# V4-AddOnZigbee-SMD-V002.net
KiCad netlist of a schematic drawn in EAGLE
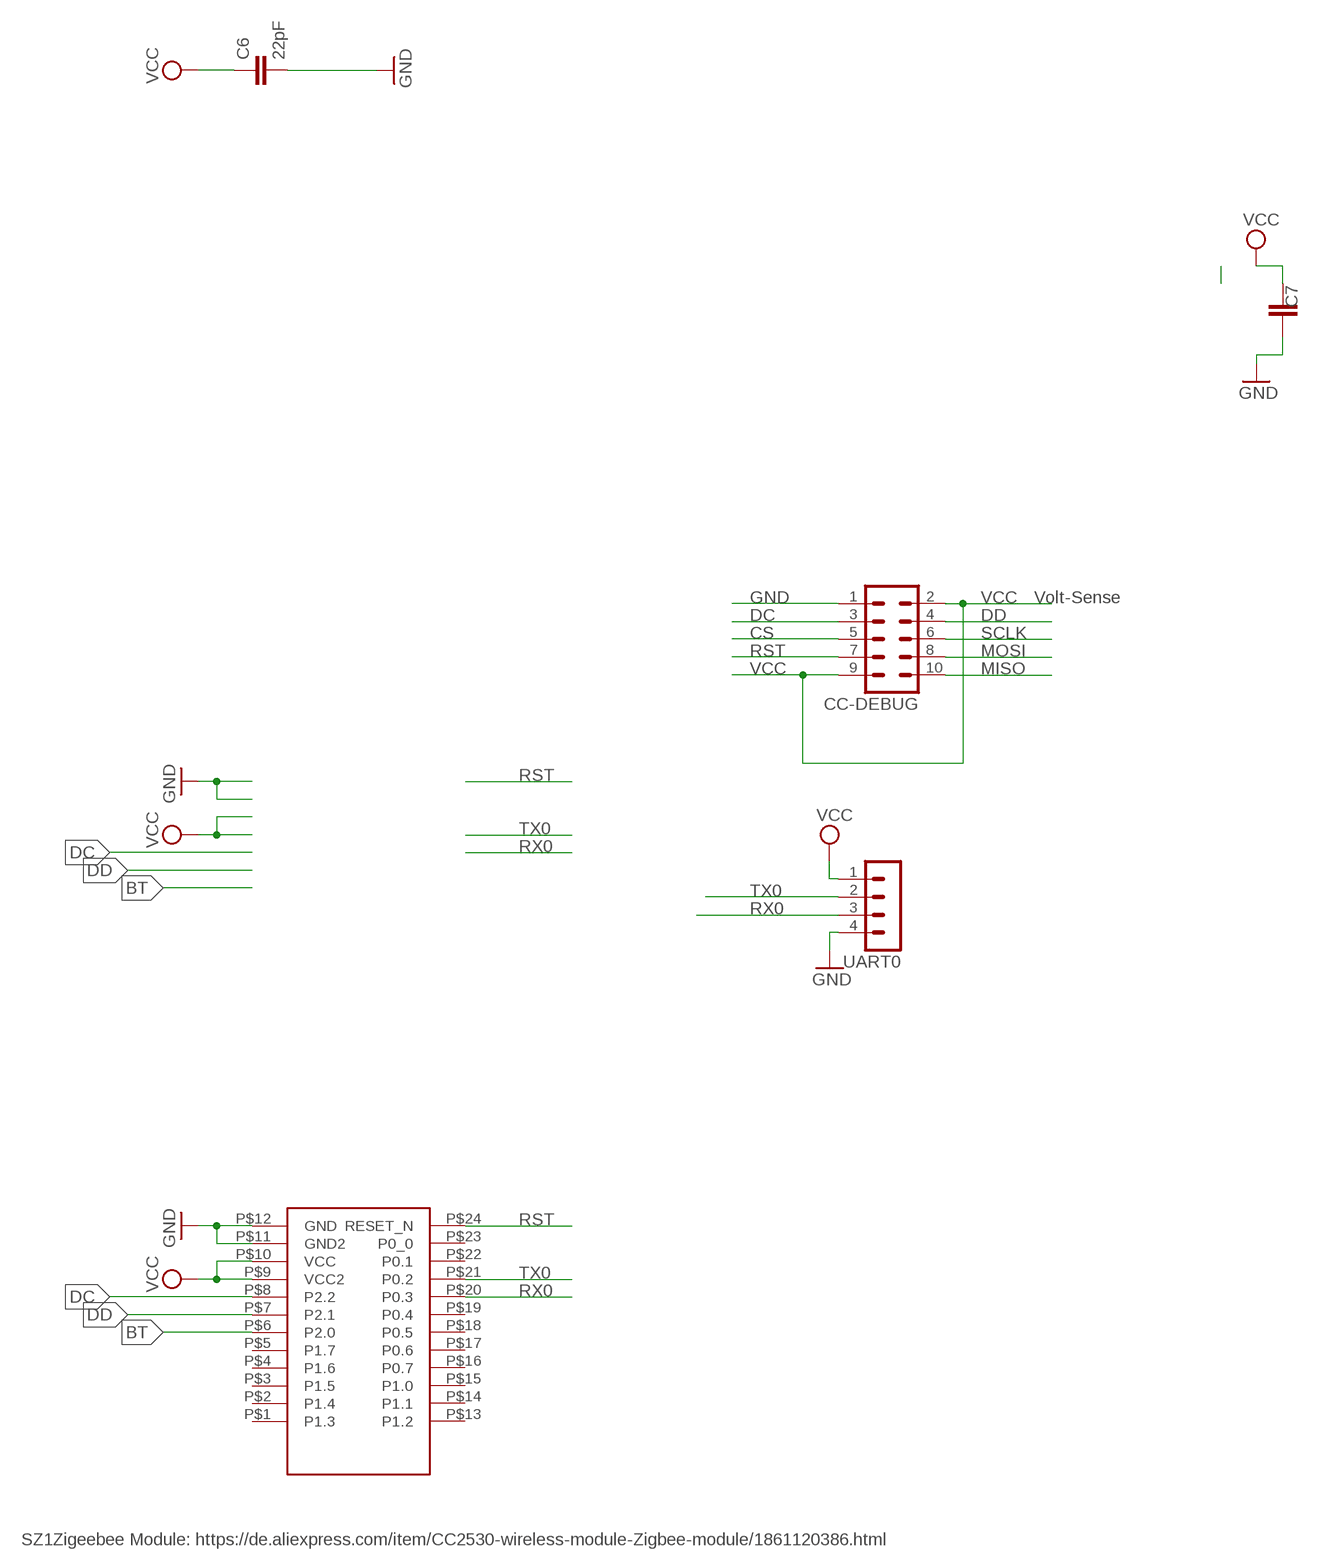
[diagram p0: schematic, sheet 1]

(export (version "E")
  (design (tool "Eeschema 10.0.6"))
  (components
    (comp (ref "C6")
      (value "22pF")
      (footprint "eagle-import:C0805")
      (libsource (lib "eagle-import") (part "C-EUC0805"))
    )
    (comp (ref "C7")
      (value "C-EUC1812")
      (footprint "eagle-import:C1812")
      (libsource (lib "eagle-import") (part "C-EUC1812"))
    )
    (comp (ref "CC-DEBUG")
      (value "MA05-2")
      (footprint "eagle-import:MA05-2")
      (libsource (lib "eagle-import") (part "MA05-2"))
    )
    (comp (ref "U$1")
      (value "CC2530")
      (footprint "eagle-import:SZ1ZIGBEE-SMD")
      (libsource (lib "eagle-import") (part "CC2530"))
    )
    (comp (ref "UART0")
      (value "MA04-1")
      (footprint "eagle-import:MA04-1")
      (libsource (lib "eagle-import") (part "MA04-1"))
    )
  )
  (nets
    (net (code "1") (name "/CS") (class "Default")
      (node (ref "CC-DEBUG") (pin "5") (pinfunction "5_5") (pintype "passive"))
    )
    (net (code "2") (name "/MISO") (class "Default")
      (node (ref "CC-DEBUG") (pin "10") (pinfunction "10_10") (pintype "passive"))
    )
    (net (code "3") (name "/MOSI") (class "Default")
      (node (ref "CC-DEBUG") (pin "8") (pinfunction "8_8") (pintype "passive"))
    )
    (net (code "4") (name "/RST") (class "Default")
      (node (ref "CC-DEBUG") (pin "7") (pinfunction "7_7") (pintype "passive"))
      (node (ref "U$1") (pin "P$24") (pinfunction "RESET_N_P$24") (pintype "bidirectional"))
    )
    (net (code "5") (name "/RX0") (class "Default")
      (node (ref "U$1") (pin "P$20") (pinfunction "P0.3_P$20") (pintype "bidirectional"))
      (node (ref "UART0") (pin "3") (pinfunction "3_3") (pintype "passive"))
    )
    (net (code "6") (name "/SCLK") (class "Default")
      (node (ref "CC-DEBUG") (pin "6") (pinfunction "6_6") (pintype "passive"))
    )
    (net (code "7") (name "/TX0") (class "Default")
      (node (ref "U$1") (pin "P$21") (pinfunction "P0.2_P$21") (pintype "bidirectional"))
      (node (ref "UART0") (pin "2") (pinfunction "2_2") (pintype "passive"))
    )
    (net (code "8") (name "BT") (class "Default")
      (node (ref "U$1") (pin "P$6") (pinfunction "P2.0_P$6") (pintype "bidirectional"))
    )
    (net (code "9") (name "DC") (class "Default")
      (node (ref "CC-DEBUG") (pin "3") (pinfunction "3_3") (pintype "passive"))
      (node (ref "U$1") (pin "P$8") (pinfunction "P2.2_P$8") (pintype "bidirectional"))
    )
    (net (code "10") (name "DD") (class "Default")
      (node (ref "CC-DEBUG") (pin "4") (pinfunction "4_4") (pintype "passive"))
      (node (ref "U$1") (pin "P$7") (pinfunction "P2.1_P$7") (pintype "bidirectional"))
    )
    (net (code "11") (name "GND") (class "Default")
      (node (ref "C6") (pin "2") (pinfunction "2_2") (pintype "passive"))
      (node (ref "C7") (pin "1") (pinfunction "1_1") (pintype "passive"))
      (node (ref "CC-DEBUG") (pin "1") (pinfunction "1_1") (pintype "passive"))
      (node (ref "U$1") (pin "P$11") (pinfunction "GND2_P$11") (pintype "bidirectional"))
      (node (ref "U$1") (pin "P$12") (pinfunction "GND_P$12") (pintype "bidirectional"))
      (node (ref "UART0") (pin "4") (pinfunction "4_4") (pintype "passive"))
    )
    (net (code "12") (name "VCC") (class "Default")
      (node (ref "C6") (pin "1") (pinfunction "1_1") (pintype "passive"))
      (node (ref "C7") (pin "2") (pinfunction "2_2") (pintype "passive"))
      (node (ref "CC-DEBUG") (pin "2") (pinfunction "2_2") (pintype "passive"))
      (node (ref "CC-DEBUG") (pin "9") (pinfunction "9_9") (pintype "passive"))
      (node (ref "U$1") (pin "P$10") (pinfunction "VCC_P$10") (pintype "bidirectional"))
      (node (ref "U$1") (pin "P$9") (pinfunction "VCC2_P$9") (pintype "bidirectional"))
      (node (ref "UART0") (pin "1") (pinfunction "1_1") (pintype "passive"))
    )
    (net (code "13") (name "unconnected-(U$1-P0.1-PadP$22)") (class "Default")
      (node (ref "U$1") (pin "P$22") (pinfunction "P0.1_P$22") (pintype "bidirectional"))
    )
    (net (code "14") (name "unconnected-(U$1-P0.4-PadP$19)") (class "Default")
      (node (ref "U$1") (pin "P$19") (pinfunction "P0.4_P$19") (pintype "bidirectional"))
    )
    (net (code "15") (name "unconnected-(U$1-P0.5-PadP$18)") (class "Default")
      (node (ref "U$1") (pin "P$18") (pinfunction "P0.5_P$18") (pintype "bidirectional"))
    )
    (net (code "16") (name "unconnected-(U$1-P0.6-PadP$17)") (class "Default")
      (node (ref "U$1") (pin "P$17") (pinfunction "P0.6_P$17") (pintype "bidirectional"))
    )
    (net (code "17") (name "unconnected-(U$1-P0.7-PadP$16)") (class "Default")
      (node (ref "U$1") (pin "P$16") (pinfunction "P0.7_P$16") (pintype "bidirectional"))
    )
    (net (code "18") (name "unconnected-(U$1-P0_0-PadP$23)") (class "Default")
      (node (ref "U$1") (pin "P$23") (pinfunction "P0_0_P$23") (pintype "bidirectional"))
    )
    (net (code "19") (name "unconnected-(U$1-P1.0-PadP$15)") (class "Default")
      (node (ref "U$1") (pin "P$15") (pinfunction "P1.0_P$15") (pintype "bidirectional"))
    )
    (net (code "20") (name "unconnected-(U$1-P1.1-PadP$14)") (class "Default")
      (node (ref "U$1") (pin "P$14") (pinfunction "P1.1_P$14") (pintype "bidirectional"))
    )
    (net (code "21") (name "unconnected-(U$1-P1.2-PadP$13)") (class "Default")
      (node (ref "U$1") (pin "P$13") (pinfunction "P1.2_P$13") (pintype "bidirectional"))
    )
    (net (code "22") (name "unconnected-(U$1-P1.3-PadP$1)") (class "Default")
      (node (ref "U$1") (pin "P$1") (pinfunction "P1.3_P$1") (pintype "bidirectional"))
    )
    (net (code "23") (name "unconnected-(U$1-P1.4-PadP$2)") (class "Default")
      (node (ref "U$1") (pin "P$2") (pinfunction "P1.4_P$2") (pintype "bidirectional"))
    )
    (net (code "24") (name "unconnected-(U$1-P1.5-PadP$3)") (class "Default")
      (node (ref "U$1") (pin "P$3") (pinfunction "P1.5_P$3") (pintype "bidirectional"))
    )
    (net (code "25") (name "unconnected-(U$1-P1.6-PadP$4)") (class "Default")
      (node (ref "U$1") (pin "P$4") (pinfunction "P1.6_P$4") (pintype "bidirectional"))
    )
    (net (code "26") (name "unconnected-(U$1-P1.7-PadP$5)") (class "Default")
      (node (ref "U$1") (pin "P$5") (pinfunction "P1.7_P$5") (pintype "bidirectional"))
    )
  )
)
